# High_Voltage_Section.net
KiCad netlist of a schematic drawn in Altium Designer
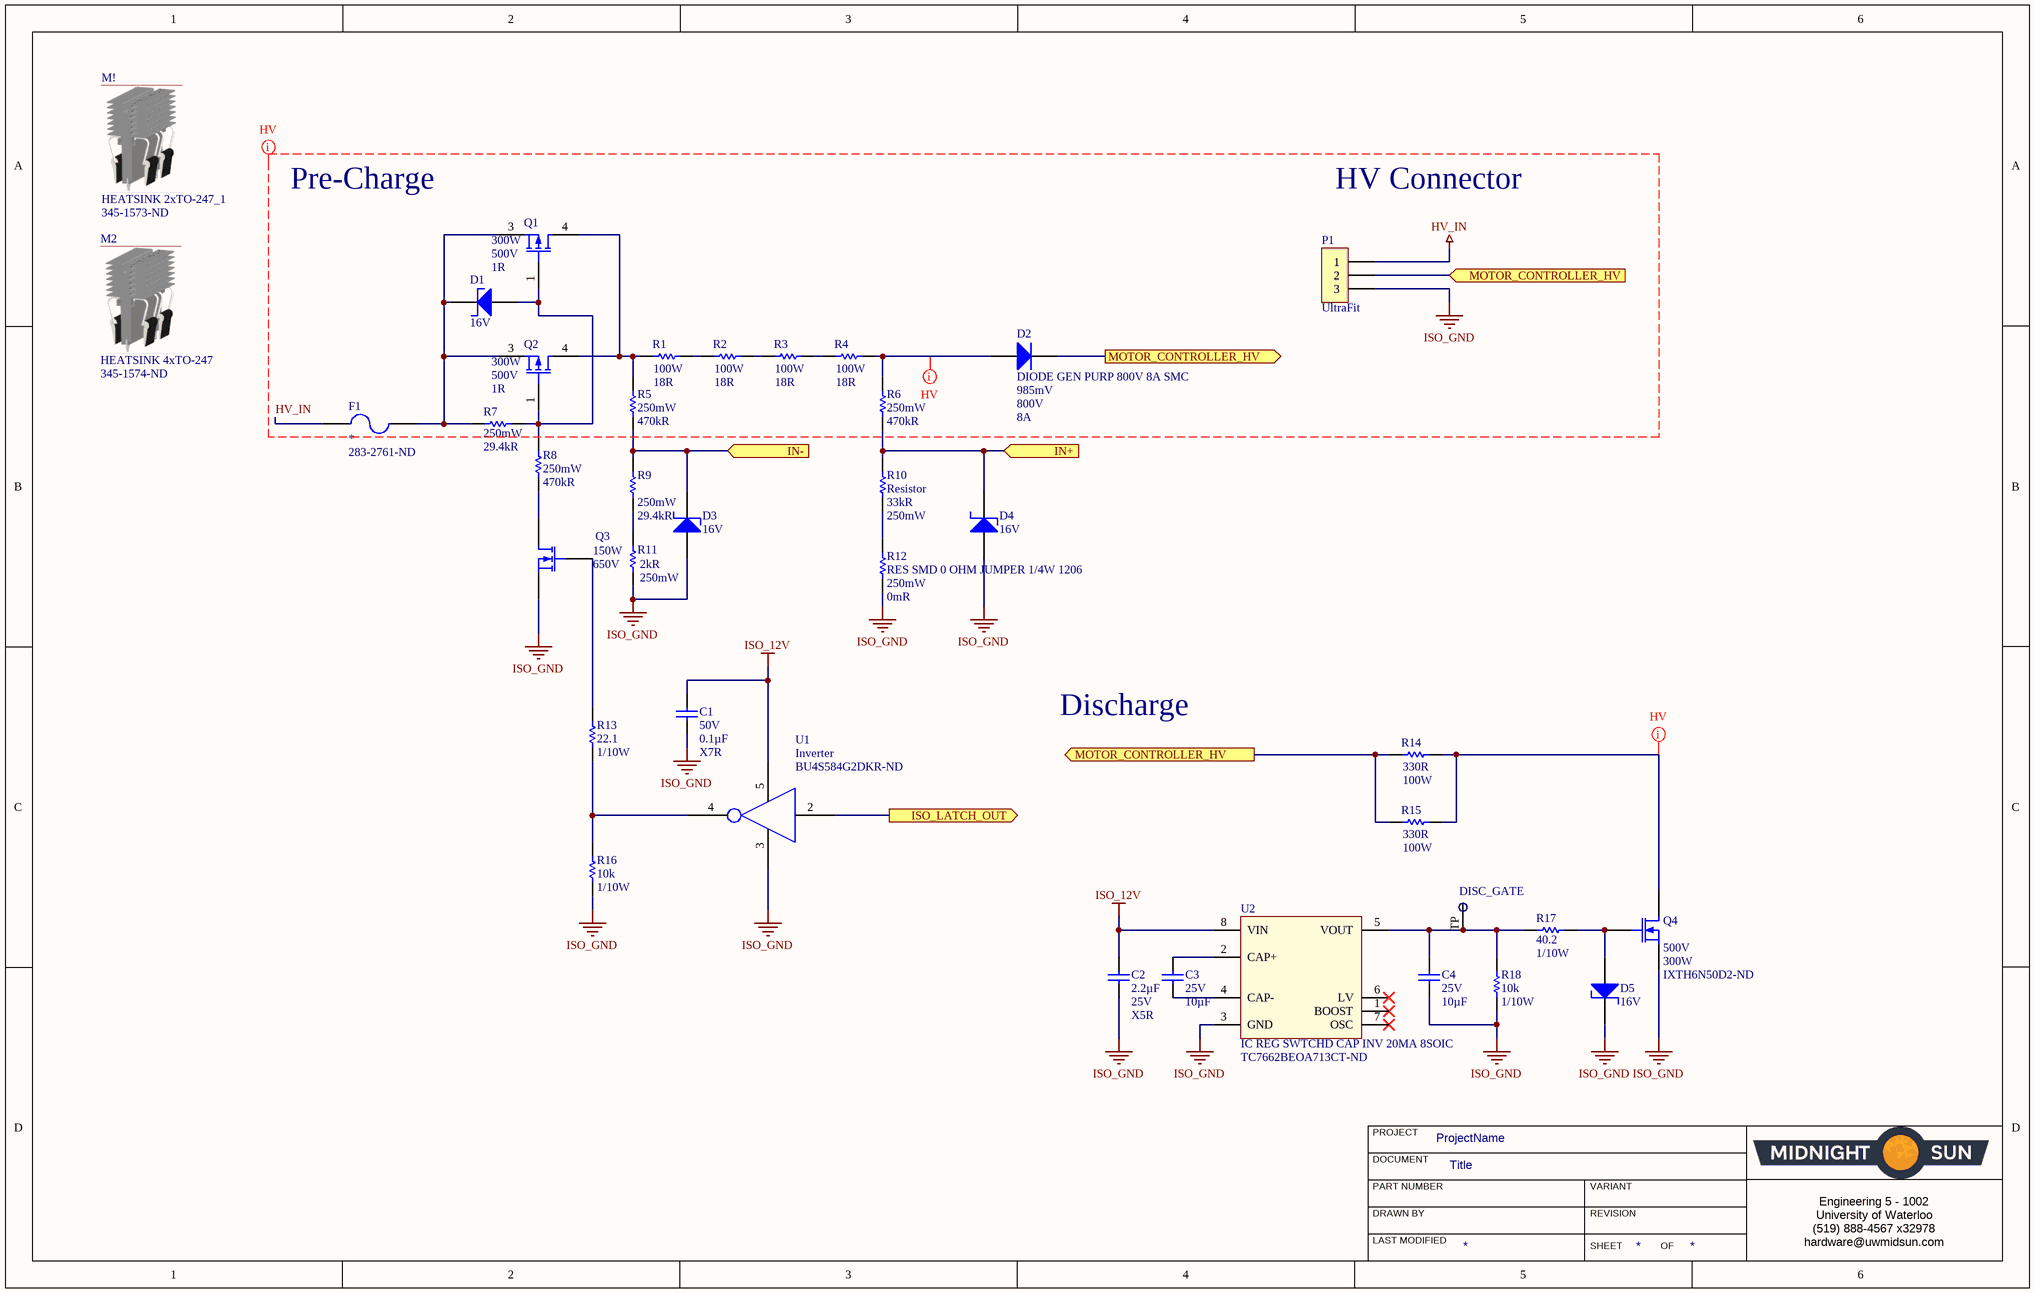
[diagram p0: High Voltage Section.SchDoc]

(export (version "E")
  (design (tool "Eeschema 10.0.6"))
  (components
    (comp (ref "C1")
      (value "CAP CER 0.1UF 50V 10% X7R 0603")
      (footprint "CAP, 0603")
      (description "0.10µF ±10% 50V Ceramic Capacitor X7R 0603 (1608 Metric)")
      (fields
        (field (name "VOLTAGE") "50V")
        (field (name "TOLERANCE") "±10%")
        (field (name "CAPACITANCE") "0.1µF")
        (field (name "TEMPERATURE COEFFICIENT") "X7R")
      )
      (libsource (lib "Schematic Diagrams") (part "CAP CER 0.1UF 50V 10% X7R 0603"))
    )
    (comp (ref "C2")
      (value "CAP CER 2.2UF 25V 10% X5R 0603")
      (footprint "CAP, 0603")
      (description "2.2µF ±10% 25V Ceramic Capacitor X5R 0603 (1608 Metric)")
      (fields
        (field (name "TOLERANCE") "±10%")
        (field (name "CAPACITANCE") "2.2µF")
        (field (name "VOLTAGE") "25V")
        (field (name "TEMPERATURE COEFFICIENT") "X5R")
      )
      (libsource (lib "Schematic Diagrams") (part "CAP CER 2.2UF 25V 10% X5R 0603"))
    )
    (comp (ref "C3")
      (value "CAP CER 10uF 25V 10% X5R 0805")
      (footprint "CAP, 0805")
      (description "10µF ±10% 25V Ceramic Capacitor X5R 0805 (2012 Metric)")
      (fields
        (field (name "MANUFACTURER") "Murata Electronics North America")
        (field (name "MANUFACTURER PART NUMBER") "GRM21BR61E106KA73L")
        (field (name "VOLTAGE - RATED") "25V")
        (field (name "CAPACITANCE") "10µF")
      )
      (libsource (lib "Schematic Diagrams") (part "CAP CER 10uF 25V 10% X5R 0805"))
    )
    (comp (ref "C4")
      (value "CAP CER 10uF 25V 10% X5R 0805")
      (footprint "CAP, 0805")
      (description "10µF ±10% 25V Ceramic Capacitor X5R 0805 (2012 Metric)")
      (fields
        (field (name "MANUFACTURER") "Murata Electronics North America")
        (field (name "MANUFACTURER PART NUMBER") "GRM21BR61E106KA73L")
        (field (name "VOLTAGE - RATED") "25V")
        (field (name "CAPACITANCE") "10µF")
      )
      (libsource (lib "Schematic Diagrams") (part "CAP CER 10uF 25V 10% X5R 0805"))
    )
    (comp (ref "D1")
      (value "DIODE ZENER 16V 5W DO-214AA (SMB)")
      (footprint "DO-214AA Diode")
      (description "Zener Diode 16V 5W ±5% Surface Mount DO-214AA (SMB)")
      (fields
        (field (name "MANUFACTURE PART NUMBER") "SMBJ5353B-TP")
        (field (name "VOLTAGE - ZENER (NOM)") "16V")
      )
      (libsource (lib "Schematic Diagrams") (part "DIODE ZENER 16V 5W DO-214AA (SMB)"))
    )
    (comp (ref "D2")
      (value "DIODE GEN PURP 800V 8A SMC")
      (footprint "DIODE, SMC")
      (fields
        (field (name "MANUFACTURER") "Diodes")
        (field (name "MANUFACTURER PART NUMBER") "S8KC-13")
        (field (name "FORWARD VOLTAGE") "985mV")
        (field (name "MAX REVERSE VOLTAGE (DC)") "800V")
        (field (name "FORWARD CURRENT") "8A")
      )
      (libsource (lib "Schematic Diagrams") (part "DIODE GEN PURP 800V 8A SMC"))
    )
    (comp (ref "D3")
      (value "DIODE ZENER 16V 5W DO-214AA (SMB)")
      (footprint "DO-214AA Diode")
      (description "Zener Diode 16V 5W ±5% Surface Mount DO-214AA (SMB)")
      (fields
        (field (name "MANUFACTURE PART NUMBER") "SMBJ5353B-TP")
        (field (name "VOLTAGE - ZENER (NOM)") "16V")
      )
      (libsource (lib "Schematic Diagrams") (part "DIODE ZENER 16V 5W DO-214AA (SMB)"))
    )
    (comp (ref "D4")
      (value "DIODE ZENER 16V 5W DO-214AA (SMB)")
      (footprint "DO-214AA Diode")
      (description "Zener Diode 16V 5W ±5% Surface Mount DO-214AA (SMB)")
      (fields
        (field (name "MANUFACTURE PART NUMBER") "SMBJ5353B-TP")
        (field (name "VOLTAGE - ZENER (NOM)") "16V")
      )
      (libsource (lib "Schematic Diagrams") (part "DIODE ZENER 16V 5W DO-214AA (SMB)"))
    )
    (comp (ref "D5")
      (value "DIODE ZENER 16V 5W DO-214AA (SMB)")
      (footprint "DO-214AA Diode")
      (description "Zener Diode 16V 5W ±5% Surface Mount DO-214AA (SMB)")
      (fields
        (field (name "MANUFACTURE PART NUMBER") "SMBJ5353B-TP")
        (field (name "VOLTAGE - ZENER (NOM)") "16V")
      )
      (libsource (lib "Schematic Diagrams") (part "DIODE ZENER 16V 5W DO-214AA (SMB)"))
    )
    (comp (ref "DISC_GATE")
      (value "Test Point")
      (footprint "Test Point")
      (libsource (lib "Schematic Diagrams") (part "Test Point"))
    )
    (comp (ref "F1")
      (value "*")
      (footprint "FUSE 5A 400VDC RADIAL")
      (description "283-2761-ND")
      (fields (field (name "SUPPLIER PART NUMBER 1") "283-2761-ND"))
      (libsource (lib "Schematic Diagrams") (part "FUSE BOARD MNT 3A 250VAC/450VDC"))
    )
    (comp (ref "M!")
      (value "HEATSINK 2xTO-247_1")
      (footprint "HEATSINK 2x TO-247")
      (description "Heat Sink TO-220, TO-247, TO-264 Aluminum Board Level, Vertical")
      (fields
        (field (name "MANUFACTURER") "Wakefield")
        (field (name "MANUFACTURER PART NUMBER") "OMNI-UNI-30-50-D")
        (field (name "SUPPLIER PART NUMBER 1") "345-1573-ND")
      )
      (libsource (lib "Schematic Diagrams") (part "HEATSINK 2xTO-247_1"))
    )
    (comp (ref "M2")
      (value "HEATSINK 4xTO-247")
      (footprint "HEATSINK 4x TO-247")
      (description "n Heat Sink TO-220, TO-247, TO-264 Aluminum Board Level, Vertical")
      (fields
        (field (name "MANUFACTURER") "Wakefield")
        (field (name "MANUFACTURER PART NUMBER") "OMNI-UNI-30-50-D")
        (field (name "SUPPLIER PART NUMBER 1") "345-1574-ND")
      )
      (libsource (lib "Schematic Diagrams") (part "HEATSINK 4xTO-247"))
    )
    (comp (ref "P1")
      (value "CONN 3POS ULTRA-FIT 0.138\"")
      (description "3 Positions Header Connector 0.138\" (3.50mm) Through Hole Tin")
      (fields (field (name "VOLTAGE") "400V") (field (name "SERIES") "UltraFit"))
      (libsource (lib "Schematic Diagrams") (part "CONN 3POS ULTRA-FIT 0.138{dblquote}"))
    )
    (comp (ref "Q1")
      (value "IXTA10P50P")
      (footprint "P-CH MOSFET 500V 10A 300W TO-263")
      (description "P-Channel 500V 10A (Tc) 300W (Tc) Surface Mount TO-263 (IXTA)")
      (fields
        (field (name "MANUFACTURER") "IXYS")
        (field (name "MAX POWER DISSIPATION") "300W")
        (field (name "RDS ON MAX") "1R")
        (field (name "DRAIN TO SOURCE VOLTAGE (VDSS)") "500V")
      )
      (libsource (lib "Schematic Diagrams") (part "MOSFET P-CH 500V 10A 300W TO-263"))
    )
    (comp (ref "Q2")
      (value "IXTA10P50P")
      (footprint "P-CH MOSFET 500V 10A 300W TO-263")
      (description "P-Channel 500V 10A (Tc) 300W (Tc) Surface Mount TO-263 (IXTA)")
      (fields
        (field (name "MANUFACTURER") "IXYS")
        (field (name "MAX POWER DISSIPATION") "300W")
        (field (name "RDS ON MAX") "1R")
        (field (name "DRAIN TO SOURCE VOLTAGE (VDSS)") "500V")
      )
      (libsource (lib "Schematic Diagrams") (part "MOSFET P-CH 500V 10A 300W TO-263"))
    )
    (comp (ref "Q3")
      (value "MOSFET N-CH 650V 8A X2 TO-263")
      (footprint "P-CH MOSFET 500V 10A 300W TO-263")
      (description "N-Channel 650V 8A (Tc) 150W (Tc) Surface Mount TO-263")
      (fields
        (field (name "MANUFACTURER") "IXYS")
        (field (name "MAX POWER DISSIPATION") "150W")
        (field (name "DRAIN TO SOURCE VOLTAGE (VDSS)") "650V")
        (field (name "MANUFACTURER PART NUMBER") "IXTA8N65X2")
      )
      (libsource (lib "Schematic Diagrams") (part "MOSFET N-CH 650V 8A X2 TO-263"))
    )
    (comp (ref "Q4")
      (value "MOSFET DEPLETION N-CH 500V 6A TO247")
      (footprint "N-CH Depletion Mode TO-247-3")
      (description "N-Channel 500V 6A (Tc) 300W (Tc) Through Hole TO-247 (IXTH)")
      (fields
        (field (name "MANUFACTURER") "IXYS")
        (field (name "MANUFACTURER PART NUMBER") "IXTH6N50D2")
        (field (name "DRAIN TO SOURCE VOLTAGE (VDSS)") "500V")
        (field (name "MAX POWER DISSIPATION") "300W")
        (field (name "SUPPLIER PART NUMBER 1") "IXTH6N50D2-ND")
      )
      (libsource (lib "Schematic Diagrams") (part "MOSFET DEPLETION N-CH 500V 6A TO247"))
    )
    (comp (ref "R1")
      (value "RES 18 OHM 100W 5% TO-247")
      (footprint "RES TO-247-2")
      (description "18 Ohms ±5% 100W Through Hole Resistor TO-247-2 Moisture Resistant, Non-Inductive Thick Film")
      (fields
        (field (name "MANUFACTURER") "Ohmite")
        (field (name "MANUFACTURER PART NUMBER") "AP10118RJ")
        (field (name "POWER RATING") "100W")
        (field (name "RESISTANCE") "18R")
      )
      (libsource (lib "Schematic Diagrams") (part "RES 18 OHM 100W 5% TO-247"))
    )
    (comp (ref "R2")
      (value "RES 18 OHM 100W 5% TO-247")
      (footprint "RES TO-247-2")
      (description "18 Ohms ±5% 100W Through Hole Resistor TO-247-2 Moisture Resistant, Non-Inductive Thick Film")
      (fields
        (field (name "MANUFACTURER") "Ohmite")
        (field (name "MANUFACTURER PART NUMBER") "AP10118RJ")
        (field (name "POWER RATING") "100W")
        (field (name "RESISTANCE") "18R")
      )
      (libsource (lib "Schematic Diagrams") (part "RES 18 OHM 100W 5% TO-247"))
    )
    (comp (ref "R3")
      (value "RES 18 OHM 100W 5% TO-247")
      (footprint "RES TO-247-2")
      (description "18 Ohms ±5% 100W Through Hole Resistor TO-247-2 Moisture Resistant, Non-Inductive Thick Film")
      (fields
        (field (name "MANUFACTURER") "Ohmite")
        (field (name "MANUFACTURER PART NUMBER") "AP10118RJ")
        (field (name "POWER RATING") "100W")
        (field (name "RESISTANCE") "18R")
      )
      (libsource (lib "Schematic Diagrams") (part "RES 18 OHM 100W 5% TO-247"))
    )
    (comp (ref "R4")
      (value "RES 18 OHM 100W 5% TO-247")
      (footprint "RES TO-247-2")
      (description "18 Ohms ±5% 100W Through Hole Resistor TO-247-2 Moisture Resistant, Non-Inductive Thick Film")
      (fields
        (field (name "MANUFACTURER") "Ohmite")
        (field (name "MANUFACTURER PART NUMBER") "AP10118RJ")
        (field (name "POWER RATING") "100W")
        (field (name "RESISTANCE") "18R")
      )
      (libsource (lib "Schematic Diagrams") (part "RES 18 OHM 100W 5% TO-247"))
    )
    (comp (ref "R5")
      (value "RESISTOR")
      (footprint "RES 1206")
      (fields
        (field (name "MANUFACTURER") "Susumu")
        (field (name "MANUFACTURER PART NUMBER") "RG3216P-4703-B-T1")
        (field (name "TOLERANCE") "0.1%")
        (field (name "MAX POWER DISSIPATION") "250mW")
        (field (name "RESISTANCE") "470kR")
      )
      (libsource (lib "Schematic Diagrams") (part "RES SMD 470K OHM 0.1% 1/4W 1206"))
    )
    (comp (ref "R6")
      (value "RESISTOR")
      (footprint "RES 1206")
      (fields
        (field (name "MANUFACTURER") "Susumu")
        (field (name "MANUFACTURER PART NUMBER") "RG3216P-4703-B-T1")
        (field (name "TOLERANCE") "0.1%")
        (field (name "MAX POWER DISSIPATION") "250mW")
        (field (name "RESISTANCE") "470kR")
      )
      (libsource (lib "Schematic Diagrams") (part "RES SMD 470K OHM 0.1% 1/4W 1206"))
    )
    (comp (ref "R7")
      (value "Resistor")
      (footprint "RES 1206")
      (description "29.4 kOhms ±1% 0.25W, 1/4W Chip Resistor 1206 (3216 Metric) Automotive AEC-Q200 Thick Film")
      (fields
        (field (name "MANUFACTURER") "Panasonic")
        (field (name "MANUFACTURER PART NUMBER") "ERJ-8ENF2942V")
        (field (name "MAX POWER DISSIPATION") "250mW")
        (field (name "RESISTANCE") "29.4kR")
      )
      (libsource (lib "Schematic Diagrams") (part "RES SMD 29.4K OHM 1% 1/4W 1206"))
    )
    (comp (ref "R8")
      (value "RESISTOR")
      (footprint "RES 1206")
      (fields
        (field (name "MANUFACTURER") "Susumu")
        (field (name "MANUFACTURER PART NUMBER") "RG3216P-4703-B-T1")
        (field (name "TOLERANCE") "0.1%")
        (field (name "MAX POWER DISSIPATION") "250mW")
        (field (name "RESISTANCE") "470kR")
      )
      (libsource (lib "Schematic Diagrams") (part "RES SMD 470K OHM 0.1% 1/4W 1206"))
    )
    (comp (ref "R9")
      (value "Resistor")
      (footprint "RES 1206")
      (description "29.4 kOhms ±1% 0.25W, 1/4W Chip Resistor 1206 (3216 Metric) Automotive AEC-Q200 Thick Film")
      (fields
        (field (name "MANUFACTURER") "Panasonic")
        (field (name "MANUFACTURER PART NUMBER") "ERJ-8ENF2942V")
        (field (name "MAX POWER DISSIPATION") "250mW")
        (field (name "RESISTANCE") "29.4kR")
      )
      (libsource (lib "Schematic Diagrams") (part "RES SMD 29.4K OHM 1% 1/4W 1206"))
    )
    (comp (ref "R10")
      (value "Resistor")
      (footprint "RES 1206")
      (description "33 kOhms ±0.1% 0.25W, 1/4W Chip Resistor 1206 (3216 Metric) Thin Film")
      (fields
        (field (name "MANUFACTURER") "Yageo")
        (field (name "MANUFACTURER PART NUMBER") "RT1206BRD0733KL")
        (field (name "RESISTANCE") "33kR")
        (field (name "MAX POWER DISSIPATION") "250mW")
      )
      (libsource (lib "Schematic Diagrams") (part "RES SMD 33K OHM 0.1% 1/4W 1206"))
    )
    (comp (ref "R11")
      (value "RES SMD 2K OHM 0.1% 1/4W 1206")
      (footprint "RES 1206")
      (description "2 kOhms ±0.1% 0.25W, 1/4W Chip Resistor 1206 (3216 Metric) Automotive AEC-Q200 Thin Film")
      (fields
        (field (name "MANUFACTURER") "Panasonic")
        (field (name "MANUFACTURER PART NUMBER") "ERA-8AEB202V")
        (field (name "MAX POWER DISSIPATION") "250mW")
        (field (name "RESISTANCE") "2kR")
      )
      (libsource (lib "Schematic Diagrams") (part "RES SMD 2K OHM 0.1% 1/4W 1206"))
    )
    (comp (ref "R12")
      (value "RES SMD 0 OHM JUMPER 1/4W 1206")
      (footprint "RES 1206")
      (description "0 Ohms Jumper 0.25W, 1/4W Chip Resistor 1206 (3216 Metric) Automotive AEC-Q200 Thick Film")
      (fields
        (field (name "MANUFACTURER") "Vishay")
        (field (name "MANUFACTURER PART NUMBER") "CRCW12060000Z0EA")
        (field (name "POWER RATING") "250mW")
        (field (name "RESISTANCE") "0mR")
      )
      (libsource (lib "Schematic Diagrams") (part "RES SMD 0 OHM JUMPER 1/4W 1206"))
    )
    (comp (ref "R13")
      (value "RES 22.1 OHM 1% 1/10W 0603")
      (footprint "RES, 0603")
      (description "22.1 Ohm ±1% 0.1W, 1/10W Chip Resistor 0603 (1608 Metric) Moisture Resistant Thick Film")
      (fields
        (field (name "TOLERANCE") "±1%")
        (field (name "RESISTANCE") "22.1")
        (field (name "POWER") "1/10W")
      )
      (libsource (lib "Schematic Diagrams") (part "RES 22.1 OHM 1% 1/10W 0603"))
    )
    (comp (ref "R14")
      (value "RES 330 OHM 100W 5% TO-247")
      (footprint "RES TO-247-2")
      (fields
        (field (name "MANUFACTURER") "Ohmite")
        (field (name "MANUFACTURER PART NUMBER") "AP101330RJ")
        (field (name "TOLERANCE") "5%")
        (field (name "MAX POWER DISSIPATION") "100W")
        (field (name "RESISTANCE") "330R")
      )
      (libsource (lib "Schematic Diagrams") (part "RES 330 OHM 100W 5% TO-247"))
    )
    (comp (ref "R15")
      (value "RES 330 OHM 100W 5% TO-247")
      (footprint "RES TO-247-2")
      (fields
        (field (name "MANUFACTURER") "Ohmite")
        (field (name "MANUFACTURER PART NUMBER") "AP101330RJ")
        (field (name "TOLERANCE") "5%")
        (field (name "MAX POWER DISSIPATION") "100W")
        (field (name "RESISTANCE") "330R")
      )
      (libsource (lib "Schematic Diagrams") (part "RES 330 OHM 100W 5% TO-247"))
    )
    (comp (ref "R16")
      (value "RES 10K OHM 1% 1/10W 0603")
      (footprint "RES, 0603")
      (description "RES SMD 10K OHM 1% 1/10W 0603")
      (fields
        (field (name "TOLERANCE") "±1%")
        (field (name "RESISTANCE") "10k")
        (field (name "POWER") "1/10W")
      )
      (libsource (lib "Schematic Diagrams") (part "RES 10K OHM 1% 1/10W 0603"))
    )
    (comp (ref "R17")
      (value "RES 40.2 OHM 0.5% 1/10W 0603")
      (footprint "RES, 0603")
      (description "RES SMD 40.2 OHM 0.5% 1/10W 0603")
      (fields
        (field (name "TOLERANCE") "±0.5%")
        (field (name "RESISTANCE") "40.2")
        (field (name "POWER") "1/10W")
      )
      (libsource (lib "Schematic Diagrams") (part "RES 40.2 OHM 0.5% 1/10W 0603"))
    )
    (comp (ref "R18")
      (value "RES 10K OHM 1% 1/10W 0603")
      (footprint "RES, 0603")
      (description "RES SMD 10K OHM 1% 1/10W 0603")
      (fields
        (field (name "TOLERANCE") "±1%")
        (field (name "RESISTANCE") "10k")
        (field (name "POWER") "1/10W")
      )
      (libsource (lib "Schematic Diagrams") (part "RES 10K OHM 1% 1/10W 0603"))
    )
    (comp (ref "U1")
      (value "Inverter")
      (footprint "SSOP5 - Inverter")
      (description "Inverter IC 1 Channel Schmitt Trigger 5-SSOP")
      (fields
        (field (name "MANUFACTURER") "Rohm")
        (field (name "MANUFACTURER PART NUMBER") "BU4S584G2-TR")
        (field (name "SUPPLIER PART NUMBER 1") "BU4S584G2DKR-ND")
      )
      (libsource (lib "Schematic Diagrams") (part "IC INVERTER SCHMITT 1CH 5SSOP"))
    )
    (comp (ref "U2")
      (value "IC REG SWTCHD CAP INV 20MA 8SOIC")
      (footprint "SOIC8")
      (fields
        (field (name "MANUFACTURER") "Microchip")
        (field (name "MANUFACTURER PART NUMBER") "TC7662BEOA713")
        (field (name "SUPPLIER PART NUMBER 1") "TC7662BEOA713CT-ND")
      )
      (libsource (lib "Schematic Diagrams") (part "IC REG SWTCHD CAP INV 20MA 8SOIC"))
    )
  )
  (nets
    (net (code "1") (name "/IN+") (class "Default")
      (node (ref "D4") (pin "2") (pinfunction "K_2") (pintype "passive"))
      (node (ref "R10") (pin "1") (pinfunction "1_1") (pintype "passive"))
      (node (ref "R6") (pin "2") (pinfunction "2_2") (pintype "passive"))
    )
    (net (code "2") (name "/IN-") (class "Default")
      (node (ref "D3") (pin "2") (pinfunction "K_2") (pintype "passive"))
      (node (ref "R5") (pin "2") (pinfunction "2_2") (pintype "passive"))
      (node (ref "R9") (pin "1") (pinfunction "1_1") (pintype "passive"))
    )
    (net (code "3") (name "/ISO_LATCH_OUT") (class "Default")
      (node (ref "U1") (pin "2") (pinfunction "INPUT_2") (pintype "passive"))
    )
    (net (code "4") (name "/MOTOR_CONTROLLER_HV") (class "Default")
      (node (ref "D2") (pin "1") (pinfunction "K_1") (pintype "passive"))
      (node (ref "P1") (pin "2") (pinfunction "2_2") (pintype "passive"))
      (node (ref "R14") (pin "1") (pinfunction "1_1") (pintype "passive"))
      (node (ref "R15") (pin "1") (pinfunction "1_1") (pintype "passive"))
    )
    (net (code "5") (name "HV_IN") (class "Default")
      (node (ref "F1") (pin "1") (pinfunction "1_1") (pintype "passive"))
      (node (ref "P1") (pin "1") (pinfunction "1_1") (pintype "passive"))
    )
    (net (code "6") (name "ISO_12V") (class "Default")
      (node (ref "C1") (pin "1") (pinfunction "1_1") (pintype "passive"))
      (node (ref "C2") (pin "2") (pinfunction "2_2") (pintype "passive"))
      (node (ref "U1") (pin "5") (pinfunction "IN+_5") (pintype "passive"))
      (node (ref "U2") (pin "8") (pinfunction "VIN_8") (pintype "power_in"))
    )
    (net (code "7") (name "ISO_GND") (class "Default")
      (node (ref "C1") (pin "2") (pinfunction "2_2") (pintype "passive"))
      (node (ref "C2") (pin "1") (pinfunction "1_1") (pintype "passive"))
      (node (ref "C4") (pin "2") (pinfunction "2_2") (pintype "passive"))
      (node (ref "D3") (pin "1") (pinfunction "A_1") (pintype "passive"))
      (node (ref "D4") (pin "1") (pinfunction "A_1") (pintype "passive"))
      (node (ref "D5") (pin "2") (pinfunction "K_2") (pintype "passive"))
      (node (ref "P1") (pin "3") (pinfunction "3_3") (pintype "passive"))
      (node (ref "Q3") (pin "3") (pinfunction "S_3") (pintype "passive"))
      (node (ref "Q4") (pin "3") (pinfunction "S_3") (pintype "passive"))
      (node (ref "R11") (pin "2") (pinfunction "2_2") (pintype "passive"))
      (node (ref "R12") (pin "2") (pinfunction "2_2") (pintype "passive"))
      (node (ref "R16") (pin "2") (pinfunction "2_2") (pintype "passive"))
      (node (ref "R18") (pin "2") (pinfunction "2_2") (pintype "passive"))
      (node (ref "U1") (pin "3") (pinfunction "IN-_3") (pintype "passive"))
      (node (ref "U2") (pin "3") (pinfunction "GND_3") (pintype "power_in"))
    )
    (net (code "8") (name "Net-(D1-A)") (class "Default")
      (node (ref "D1") (pin "1") (pinfunction "A_1") (pintype "passive"))
      (node (ref "Q1") (pin "1") (pinfunction "G_1") (pintype "passive"))
      (node (ref "Q2") (pin "1") (pinfunction "G_1") (pintype "passive"))
      (node (ref "R7") (pin "2") (pinfunction "2_2") (pintype "passive"))
      (node (ref "R8") (pin "1") (pinfunction "1_1") (pintype "passive"))
    )
    (net (code "9") (name "Net-(D1-K)") (class "Default")
      (node (ref "D1") (pin "2") (pinfunction "K_2") (pintype "passive"))
      (node (ref "F1") (pin "2") (pinfunction "2_2") (pintype "passive"))
      (node (ref "Q1") (pin "3") (pinfunction "S_3") (pintype "passive"))
      (node (ref "Q2") (pin "3") (pinfunction "S_3") (pintype "passive"))
      (node (ref "R7") (pin "1") (pinfunction "1_1") (pintype "passive"))
    )
    (net (code "10") (name "Net-(D2-A)") (class "Default")
      (node (ref "D2") (pin "2") (pinfunction "A_2") (pintype "passive"))
      (node (ref "R4") (pin "2") (pinfunction "2_2") (pintype "passive"))
      (node (ref "R6") (pin "1") (pinfunction "1_1") (pintype "passive"))
    )
    (net (code "11") (name "Net-(D5-A)") (class "Default")
      (node (ref "D5") (pin "1") (pinfunction "A_1") (pintype "passive"))
      (node (ref "Q4") (pin "1") (pinfunction "G_1") (pintype "passive"))
      (node (ref "R17") (pin "2") (pinfunction "2_2") (pintype "passive"))
    )
    (net (code "12") (name "Net-(DISC_GATE-1)") (class "Default")
      (node (ref "C4") (pin "1") (pinfunction "1_1") (pintype "passive"))
      (node (ref "DISC_GATE") (pin "TP") (pinfunction "1_TP") (pintype "passive"))
      (node (ref "R17") (pin "1") (pinfunction "1_1") (pintype "passive"))
      (node (ref "R18") (pin "1") (pinfunction "1_1") (pintype "passive"))
      (node (ref "U2") (pin "5") (pinfunction "VOUT_5") (pintype "power_in"))
    )
    (net (code "13") (name "Net-(Q1-D)") (class "Default")
      (node (ref "Q1") (pin "4") (pinfunction "D_4") (pintype "passive"))
      (node (ref "Q2") (pin "4") (pinfunction "D_4") (pintype "passive"))
      (node (ref "R1") (pin "1") (pinfunction "1_1") (pintype "passive"))
      (node (ref "R5") (pin "1") (pinfunction "1_1") (pintype "passive"))
    )
    (net (code "14") (name "Net-(Q3-D)") (class "Default")
      (node (ref "Q3") (pin "4") (pinfunction "D_4") (pintype "passive"))
      (node (ref "R8") (pin "2") (pinfunction "2_2") (pintype "passive"))
    )
    (net (code "15") (name "Net-(Q3-G)") (class "Default")
      (node (ref "Q3") (pin "1") (pinfunction "G_1") (pintype "passive"))
      (node (ref "R13") (pin "1") (pinfunction "1_1") (pintype "passive"))
    )
    (net (code "16") (name "Net-(Q4-D)") (class "Default")
      (node (ref "Q4") (pin "2") (pinfunction "D_2") (pintype "passive"))
      (node (ref "R14") (pin "2") (pinfunction "2_2") (pintype "passive"))
      (node (ref "R15") (pin "2") (pinfunction "2_2") (pintype "passive"))
    )
    (net (code "17") (name "Net-(R1-Pad2)") (class "Default")
      (node (ref "R1") (pin "2") (pinfunction "2_2") (pintype "passive"))
      (node (ref "R2") (pin "1") (pinfunction "1_1") (pintype "passive"))
    )
    (net (code "18") (name "Net-(R2-Pad2)") (class "Default")
      (node (ref "R2") (pin "2") (pinfunction "2_2") (pintype "passive"))
      (node (ref "R3") (pin "1") (pinfunction "1_1") (pintype "passive"))
    )
    (net (code "19") (name "Net-(R3-Pad2)") (class "Default")
      (node (ref "R3") (pin "2") (pinfunction "2_2") (pintype "passive"))
      (node (ref "R4") (pin "1") (pinfunction "1_1") (pintype "passive"))
    )
    (net (code "20") (name "Net-(R10-Pad2)") (class "Default")
      (node (ref "R10") (pin "2") (pinfunction "2_2") (pintype "passive"))
      (node (ref "R12") (pin "1") (pinfunction "1_1") (pintype "passive"))
    )
    (net (code "21") (name "Net-(R11-Pad1)") (class "Default")
      (node (ref "R11") (pin "1") (pinfunction "1_1") (pintype "passive"))
      (node (ref "R9") (pin "2") (pinfunction "2_2") (pintype "passive"))
    )
    (net (code "22") (name "Net-(U1-OUTPUT)") (class "Default")
      (node (ref "R13") (pin "2") (pinfunction "2_2") (pintype "passive"))
      (node (ref "R16") (pin "1") (pinfunction "1_1") (pintype "passive"))
      (node (ref "U1") (pin "4") (pinfunction "OUTPUT_4") (pintype "passive"))
    )
    (net (code "23") (name "Net-(U2-CAP+)") (class "Default")
      (node (ref "C3") (pin "1") (pinfunction "1_1") (pintype "passive"))
      (node (ref "U2") (pin "2") (pinfunction "CAP+_2") (pintype "passive"))
    )
    (net (code "24") (name "Net-(U2-CAP-)") (class "Default")
      (node (ref "C3") (pin "2") (pinfunction "2_2") (pintype "passive"))
      (node (ref "U2") (pin "4") (pinfunction "CAP-_4") (pintype "power_in"))
    )
    (net (code "25") (name "unconnected-(U2-BOOST-Pad1)") (class "Default")
      (node (ref "U2") (pin "1") (pinfunction "BOOST_1") (pintype "power_in+no_connect"))
    )
    (net (code "26") (name "unconnected-(U2-LV-Pad6)") (class "Default")
      (node (ref "U2") (pin "6") (pinfunction "LV_6") (pintype "power_in+no_connect"))
    )
    (net (code "27") (name "unconnected-(U2-OSC-Pad7)") (class "Default")
      (node (ref "U2") (pin "7") (pinfunction "OSC_7") (pintype "power_in+no_connect"))
    )
  )
)
